# IntelliRoastSch.net
KiCad netlist of a schematic drawn in EAGLE
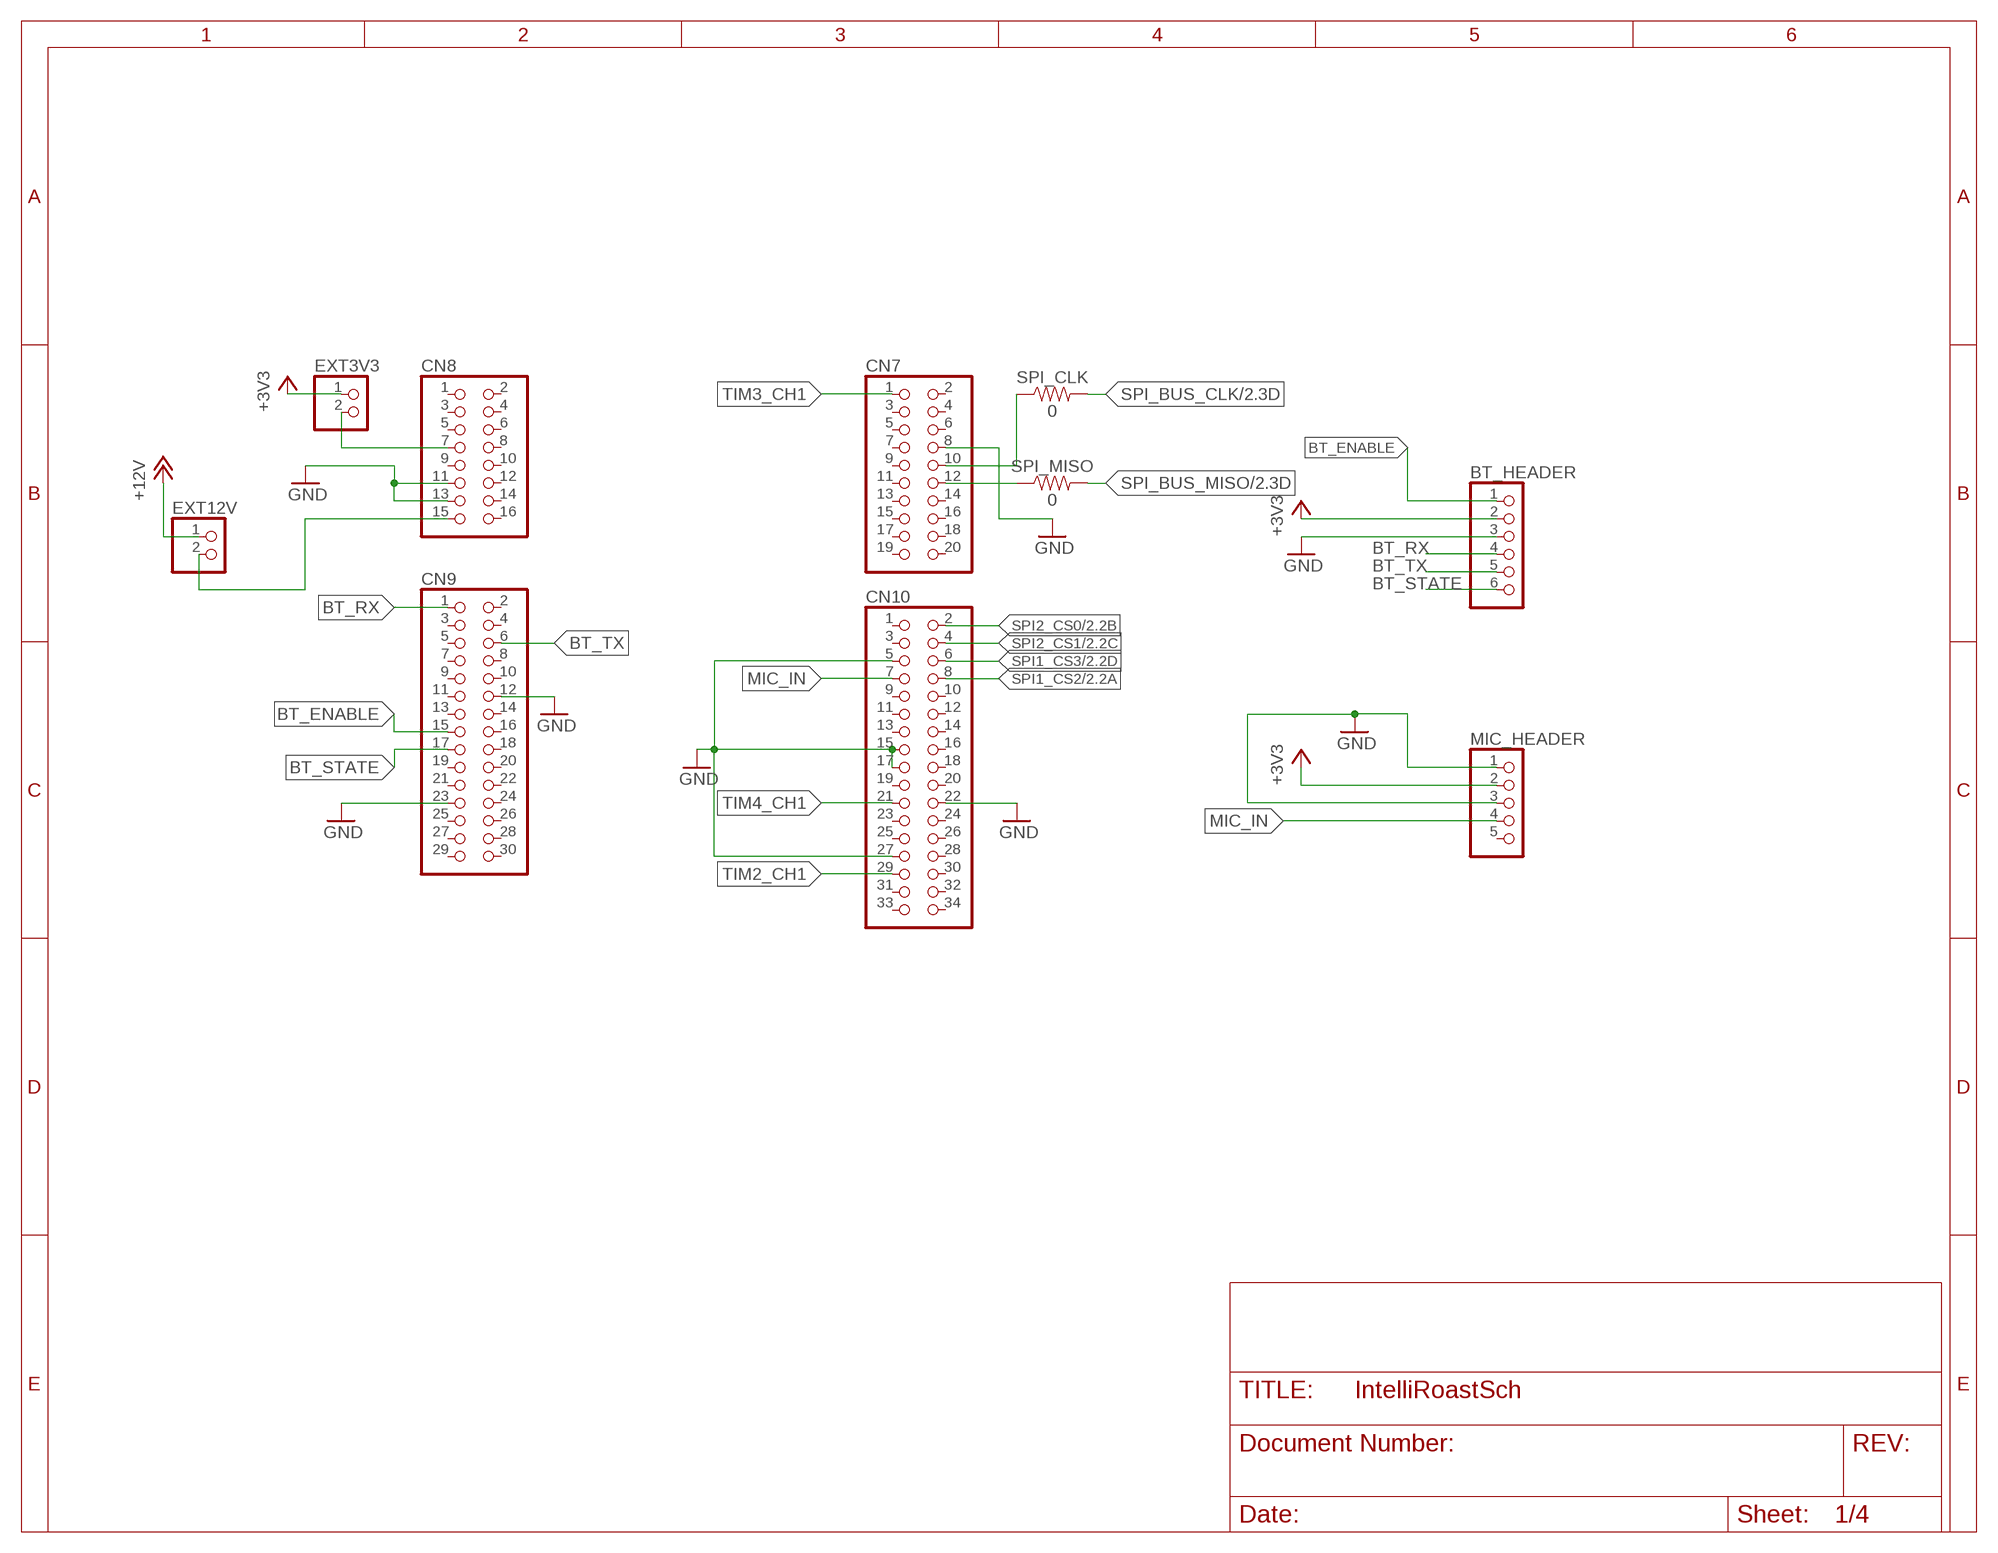
[diagram p0: schematic, sheet 1]
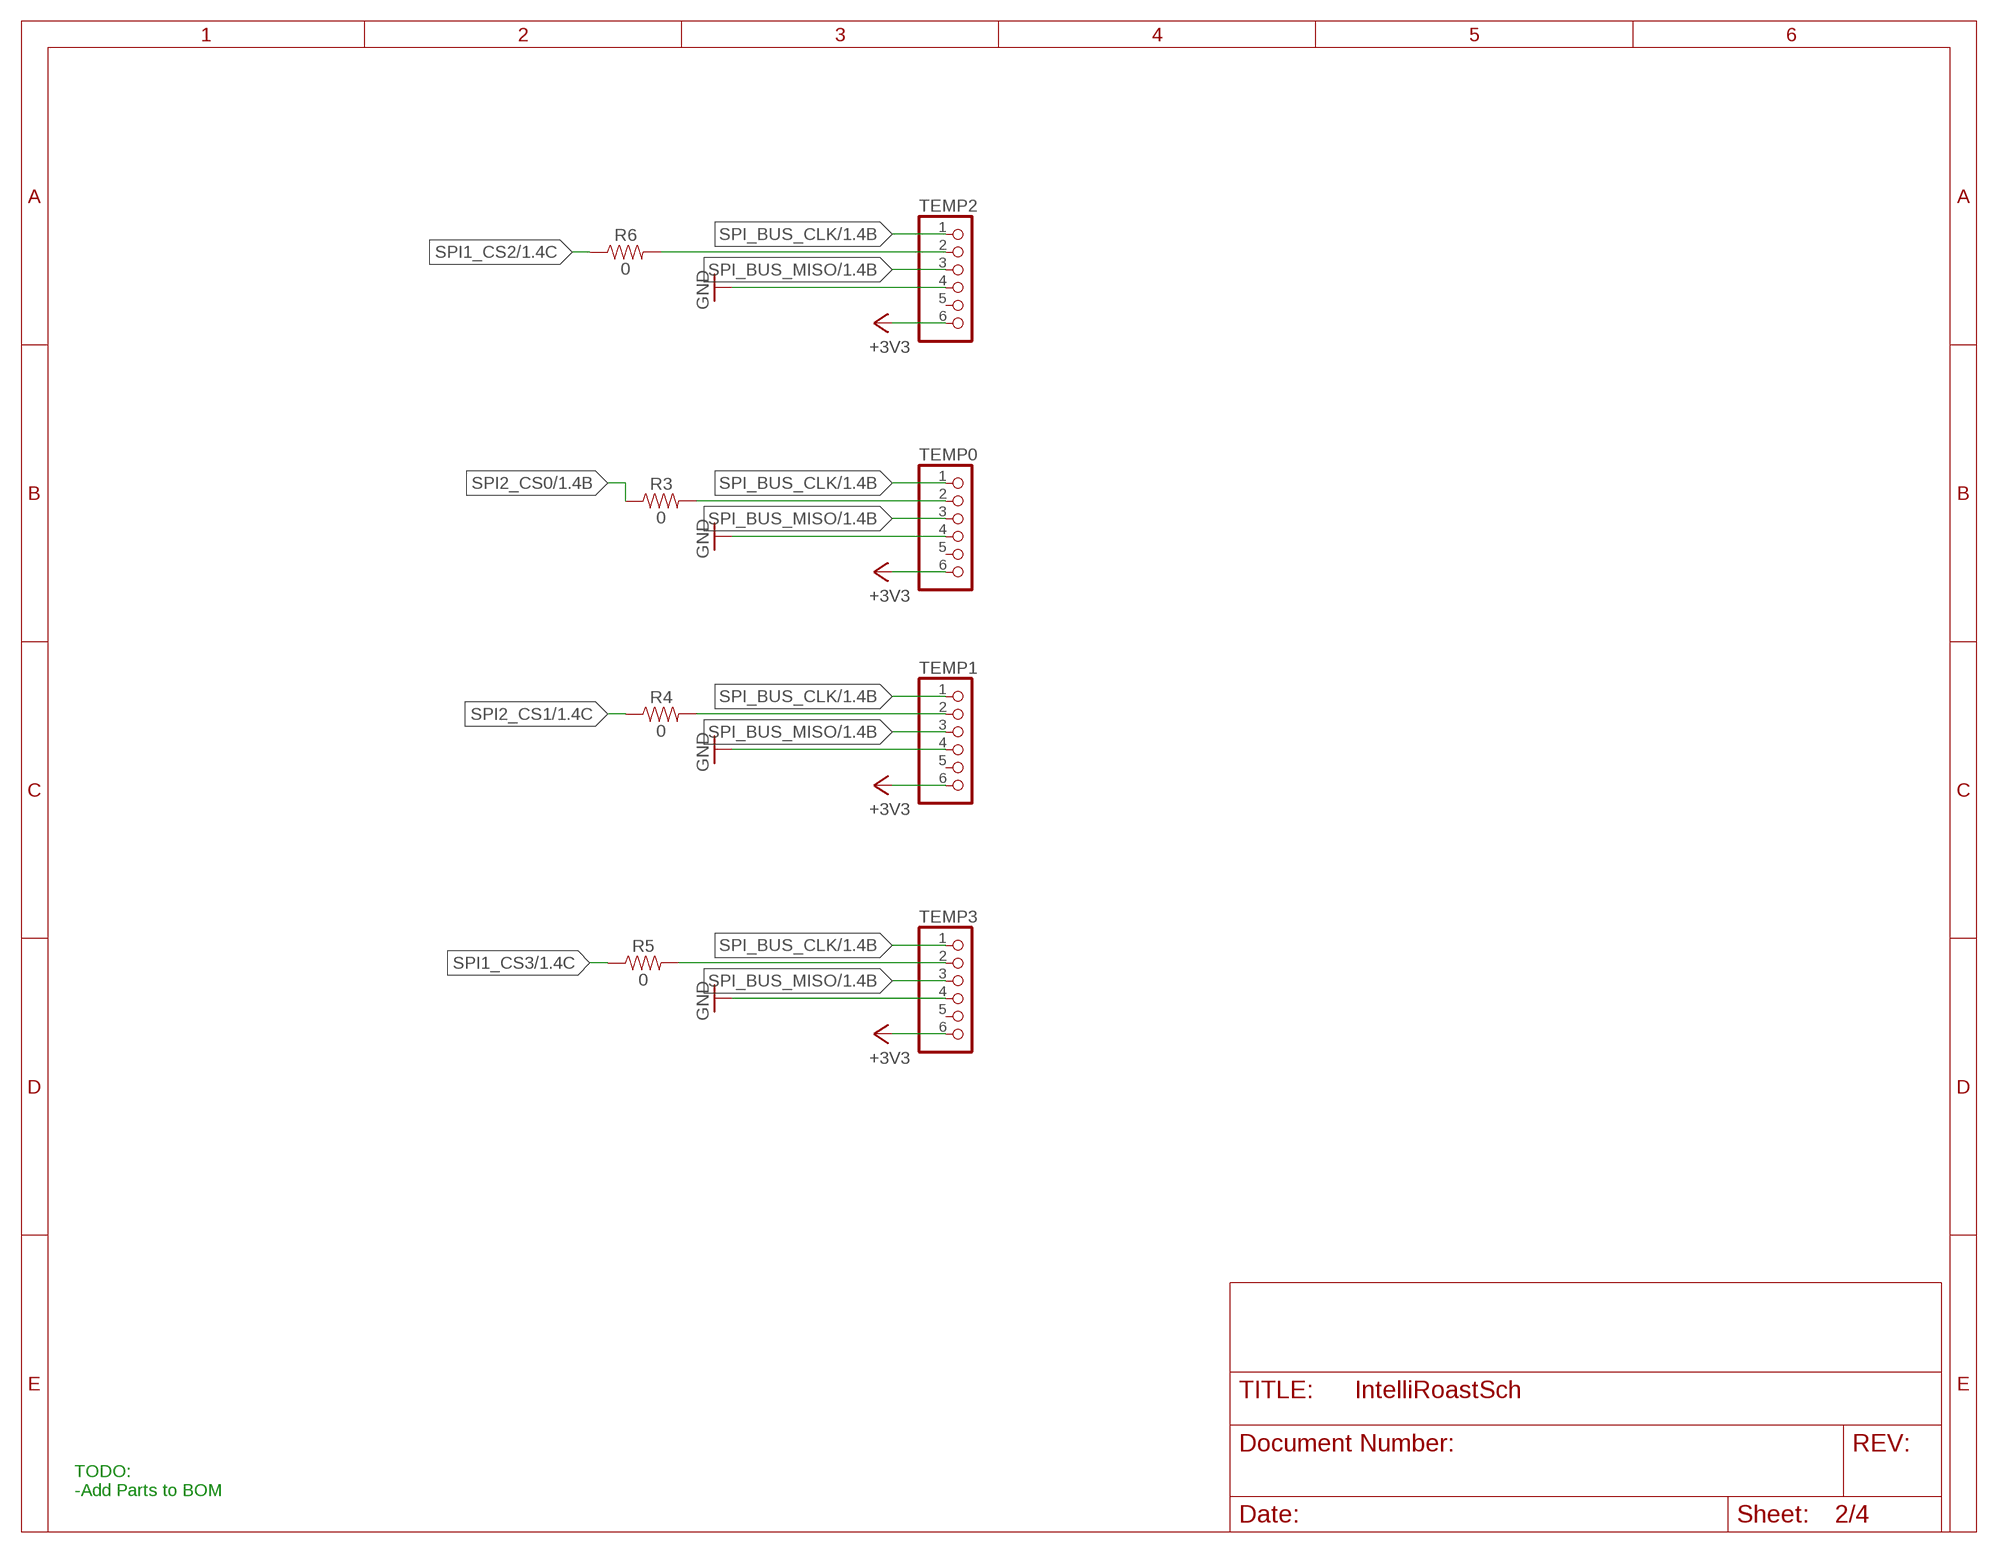
[diagram p1: schematic, sheet 2]
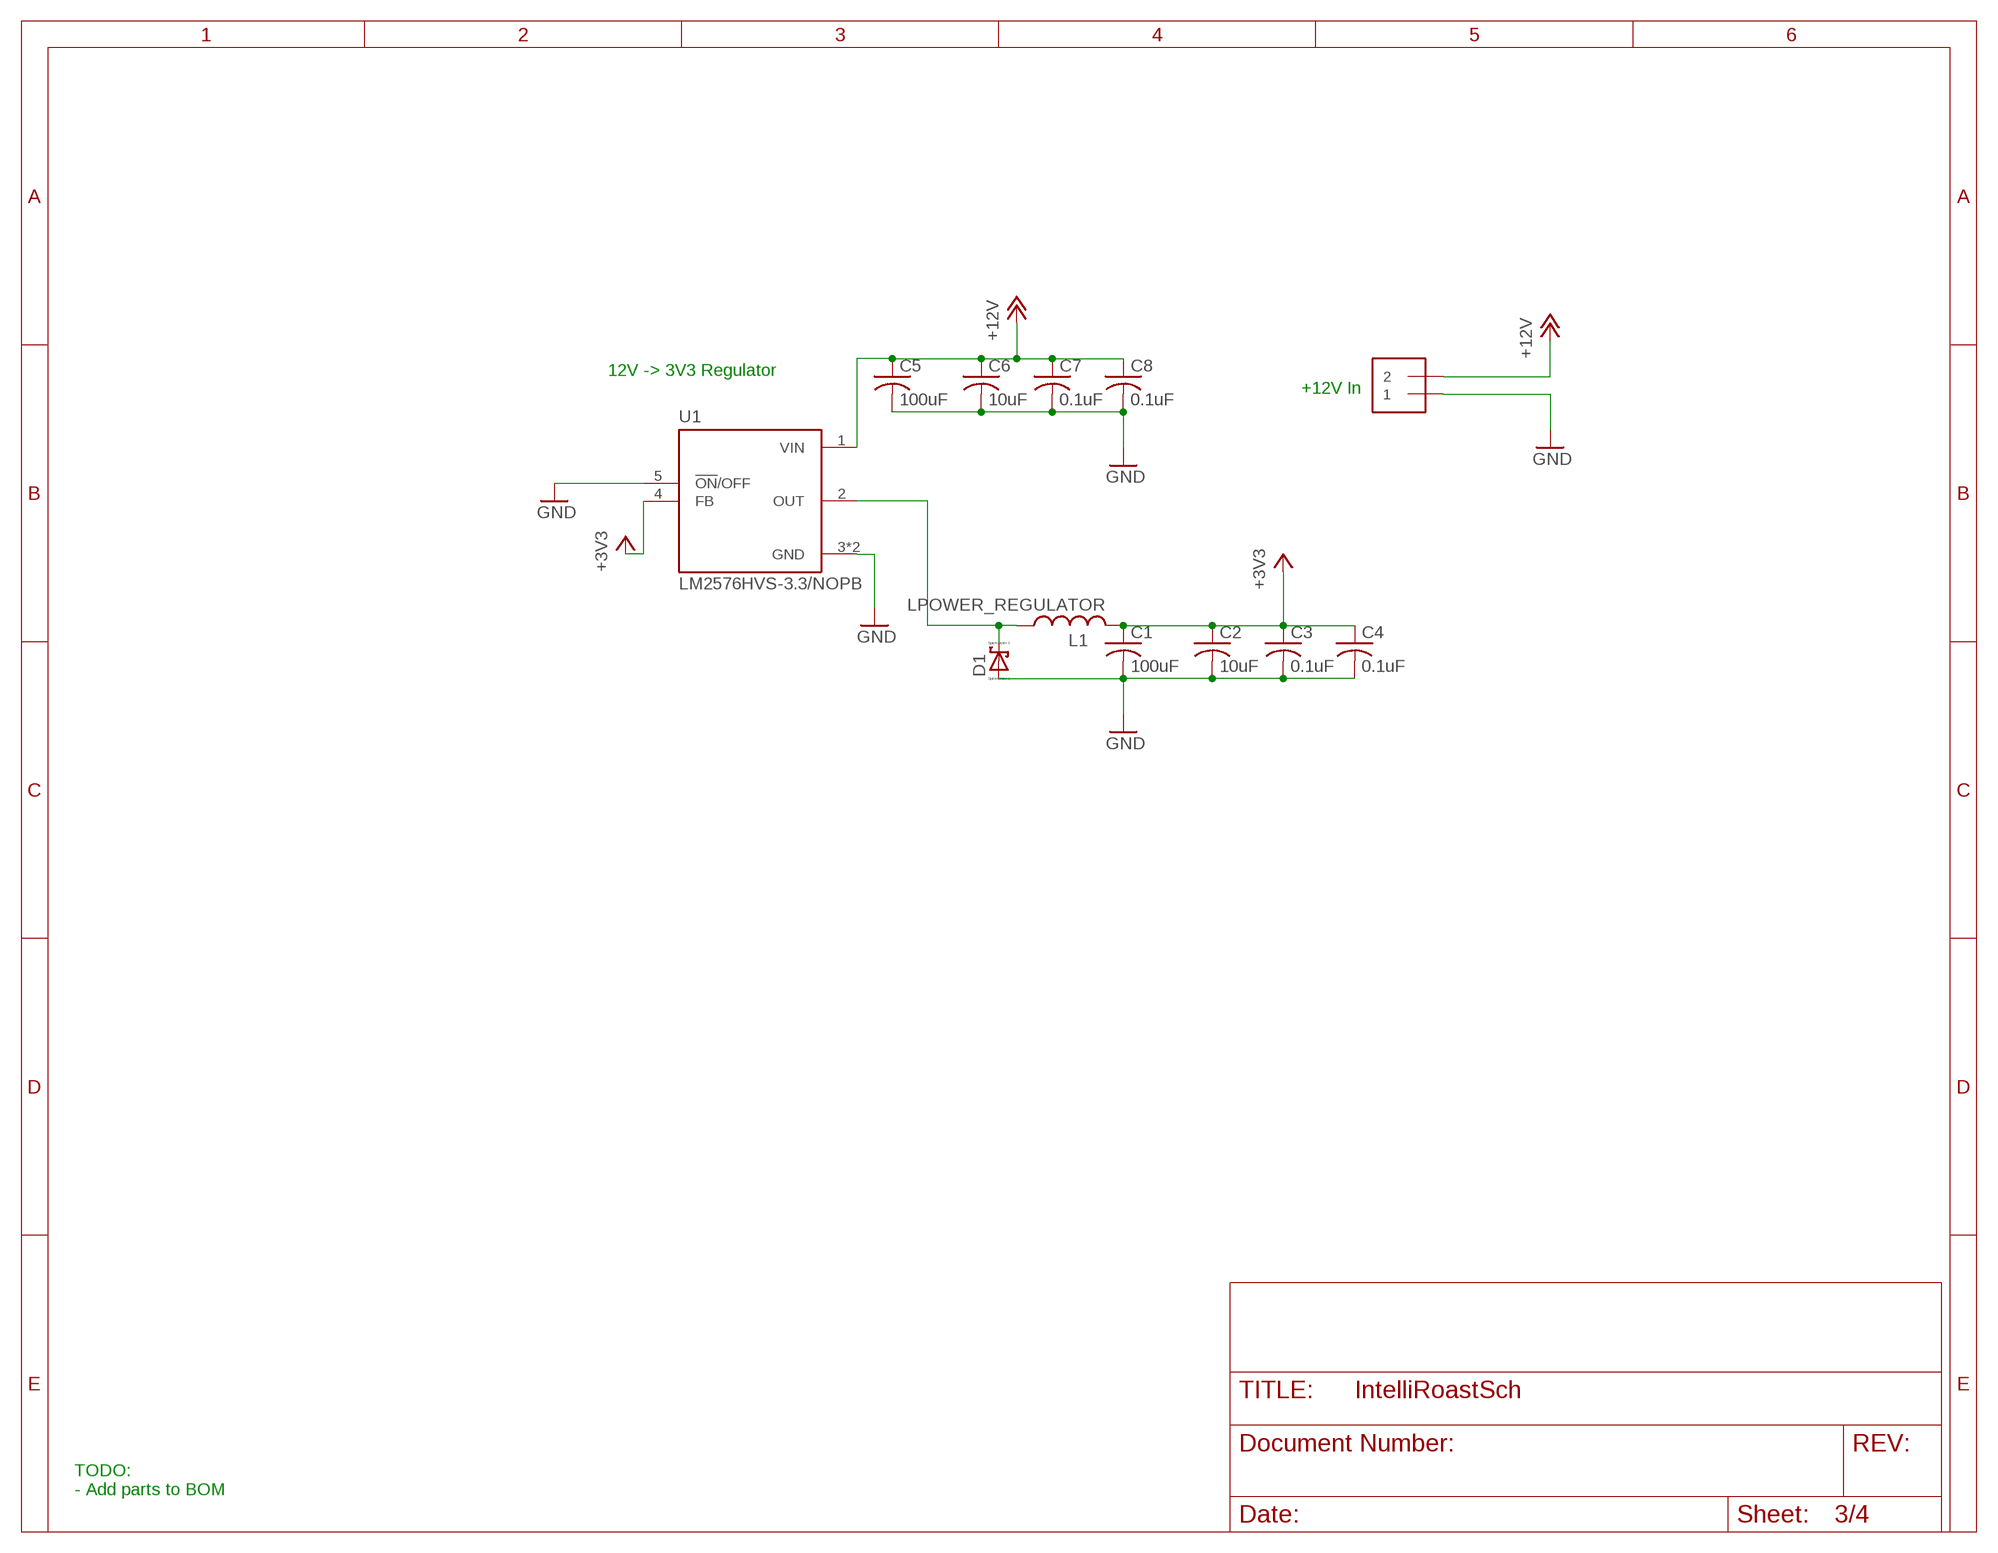
[diagram p2: schematic, sheet 3]
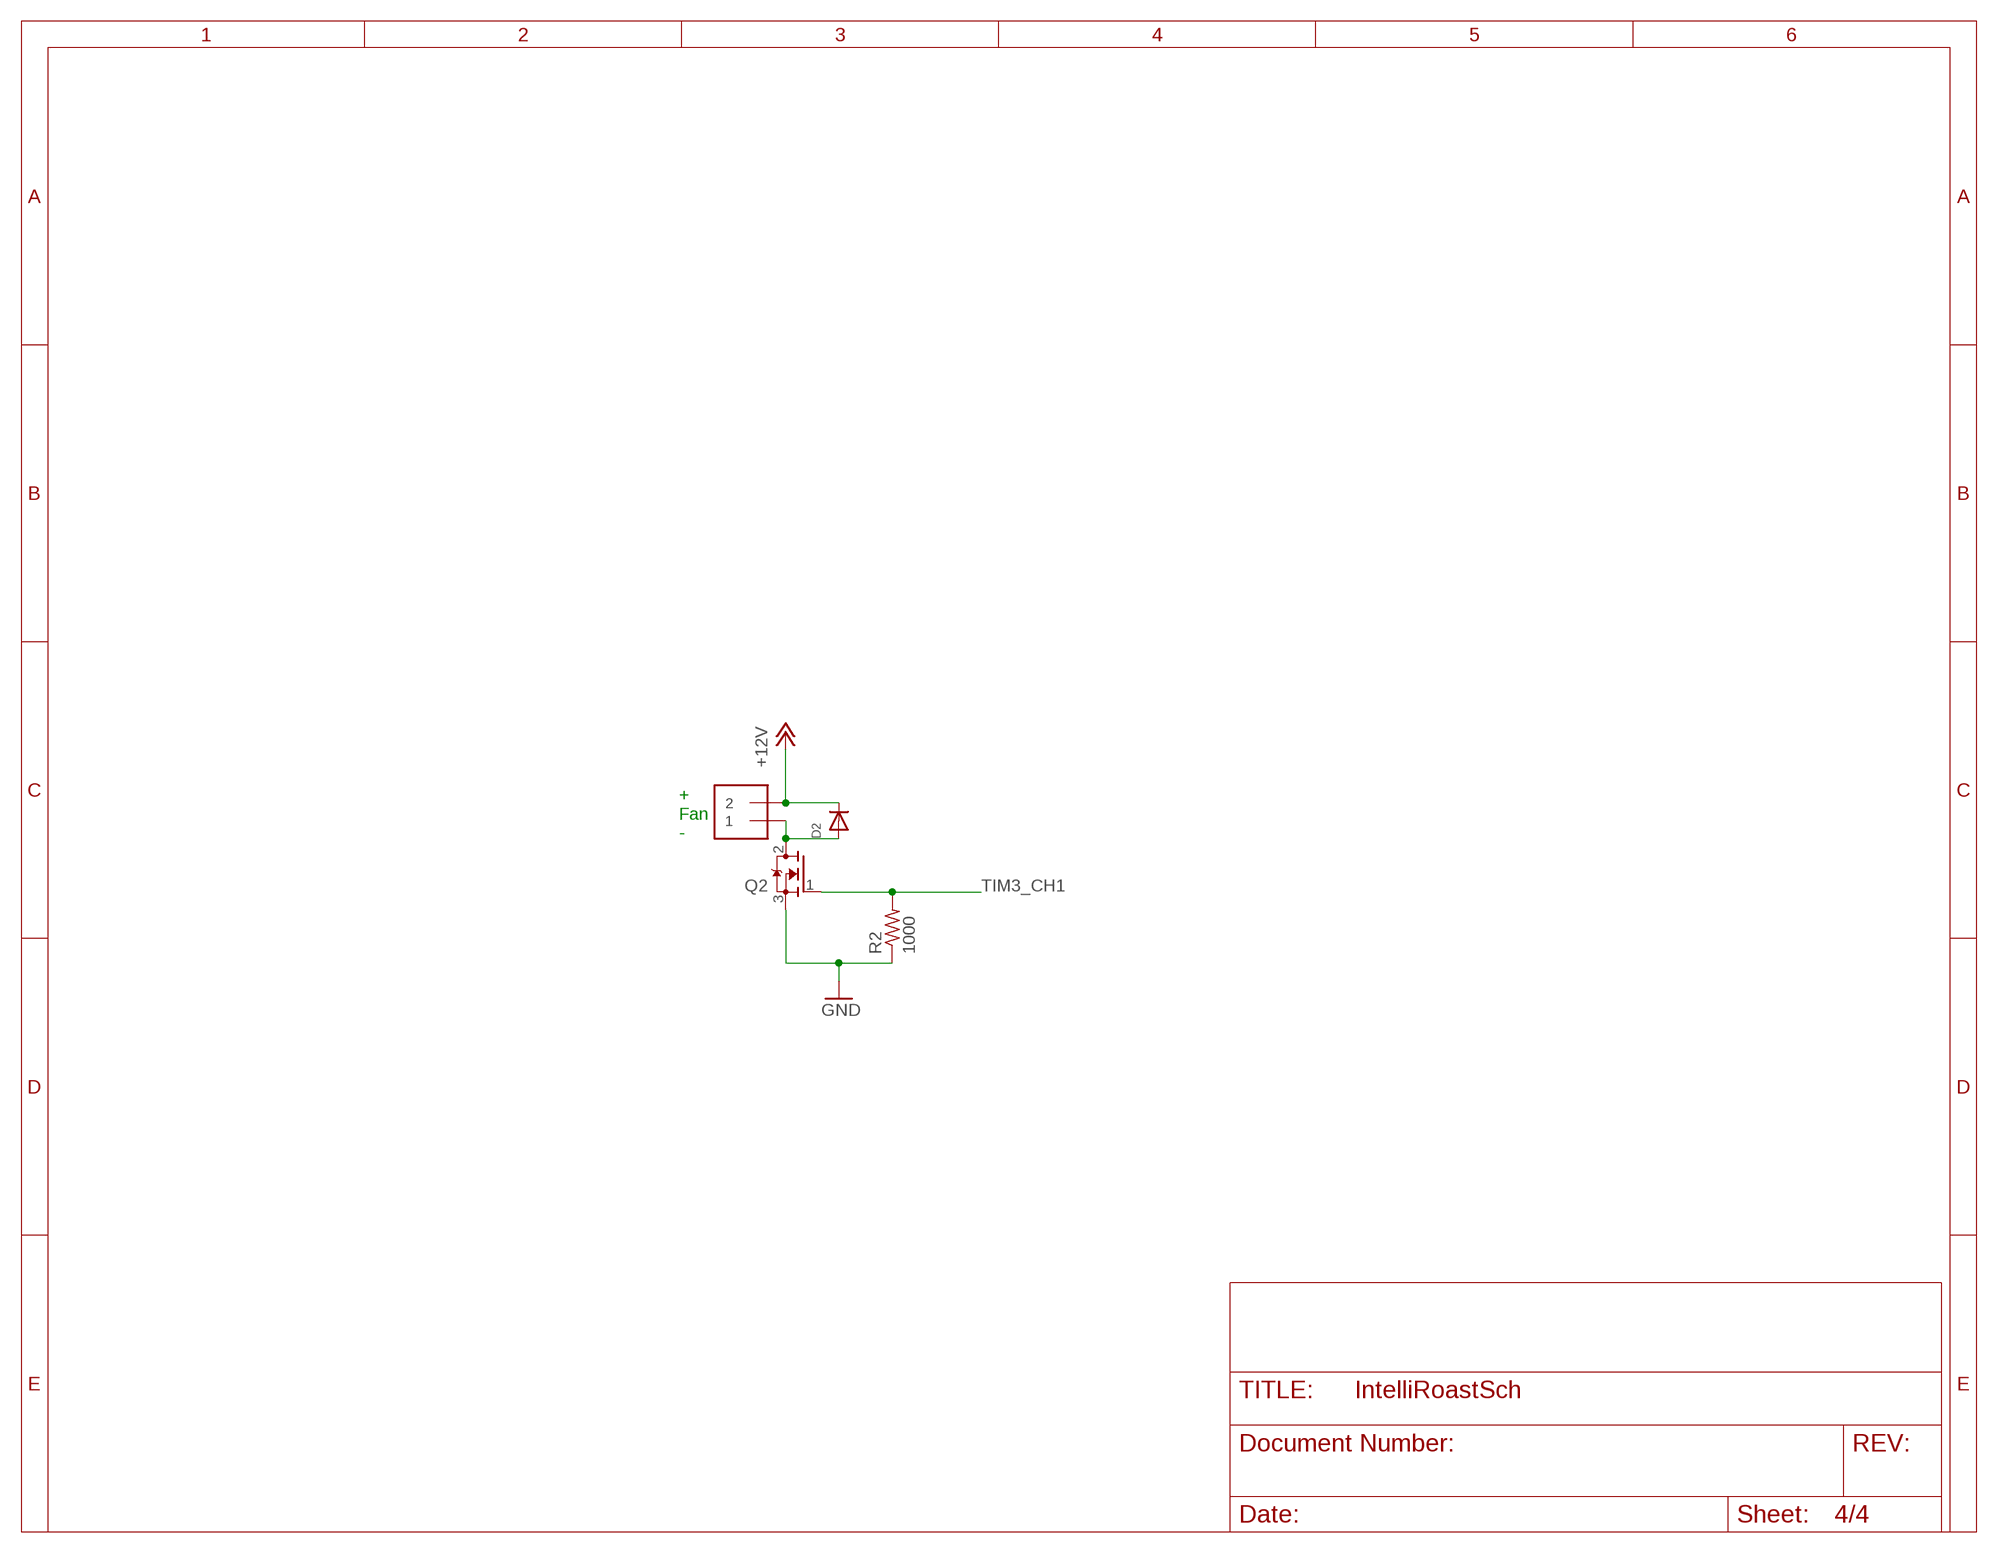
[diagram p3: schematic, sheet 4]

(export (version "E")
  (design (tool "Eeschema 10.0.6"))
  (components
    (comp (ref "C1")
      (value "100uF")
      (footprint "eagle-import:C1210")
      (libsource (lib "eagle-import") (part "C-USC1210"))
    )
    (comp (ref "C2")
      (value "10uF")
      (footprint "eagle-import:C0805")
      (libsource (lib "eagle-import") (part "C-USC0805"))
    )
    (comp (ref "C3")
      (value "0.1uF")
      (footprint "eagle-import:C0603")
      (libsource (lib "eagle-import") (part "C-USC0603"))
    )
    (comp (ref "C4")
      (value "0.1uF")
      (footprint "eagle-import:C0603")
      (libsource (lib "eagle-import") (part "C-USC0603"))
    )
    (comp (ref "C5")
      (value "100uF")
      (footprint "eagle-import:C1210")
      (libsource (lib "eagle-import") (part "C-USC1210"))
    )
    (comp (ref "C6")
      (value "10uF")
      (footprint "eagle-import:C0805")
      (libsource (lib "eagle-import") (part "C-USC0805"))
    )
    (comp (ref "C7")
      (value "0.1uF")
      (footprint "eagle-import:C0603")
      (libsource (lib "eagle-import") (part "C-USC0603"))
    )
    (comp (ref "C8")
      (value "0.1uF")
      (footprint "eagle-import:C0603")
      (libsource (lib "eagle-import") (part "C-USC0603"))
    )
    (comp (ref "D1")
      (value "SCHOTTKY-DIODESMC")
      (footprint "eagle-import:DIODE_SMC")
      (libsource (lib "eagle-import") (part "SCHOTTKY-DIODESMC"))
    )
    (comp (ref "L1")
      (value "LPOWER_REGULATOR")
      (footprint "eagle-import:L74477020")
      (libsource (lib "eagle-import") (part "LPOWER_REGULATOR"))
    )
    (comp (ref "PWR_IN")
      (value "1X2-3.5MM")
      (footprint "eagle-import:1X2-3.5MM")
      (libsource (lib "eagle-import") (part "1X2-3.5MM"))
    )
    (comp (ref "U1")
      (value "LM2576HVS-3.3/NOPB")
      (footprint "eagle-import:TO170P1435X465-6N")
      (fields (field (name "MF") "Texas Instruments"))
      (libsource (lib "eagle-import") (part "LM2576HVS-3.3/NOPB"))
    )
    (comp (ref "R3")
      (value "0")
      (footprint "eagle-import:0603")
      (libsource (lib "eagle-import") (part "0OHM-0603-1/10W-5%"))
    )
    (comp (ref "R4")
      (value "0")
      (footprint "eagle-import:0603")
      (libsource (lib "eagle-import") (part "0OHM-0603-1/10W-5%"))
    )
    (comp (ref "R5")
      (value "0")
      (footprint "eagle-import:0603")
      (libsource (lib "eagle-import") (part "0OHM-0603-1/10W-5%"))
    )
    (comp (ref "R6")
      (value "0")
      (footprint "eagle-import:0603")
      (libsource (lib "eagle-import") (part "0OHM-0603-1/10W-5%"))
    )
    (comp (ref "TEMP0")
      (value "ADAFRUIT-MAX31855-BREAKOUT")
      (footprint "eagle-import:MAX31855_HEADER")
      (libsource (lib "eagle-import") (part "ADAFRUIT-MAX31855-BREAKOUT"))
    )
    (comp (ref "TEMP1")
      (value "ADAFRUIT-MAX31855-BREAKOUT")
      (footprint "eagle-import:MAX31855_HEADER")
      (libsource (lib "eagle-import") (part "ADAFRUIT-MAX31855-BREAKOUT"))
    )
    (comp (ref "TEMP2")
      (value "ADAFRUIT-MAX31855-BREAKOUT")
      (footprint "eagle-import:MAX31855_HEADER")
      (libsource (lib "eagle-import") (part "ADAFRUIT-MAX31855-BREAKOUT"))
    )
    (comp (ref "TEMP3")
      (value "ADAFRUIT-MAX31855-BREAKOUT")
      (footprint "eagle-import:MAX31855_HEADER")
      (libsource (lib "eagle-import") (part "ADAFRUIT-MAX31855-BREAKOUT"))
    )
    (comp (ref "D2")
      (value "DIODESMA")
      (footprint "eagle-import:SMADIODE")
      (libsource (lib "eagle-import") (part "DIODESMA"))
    )
    (comp (ref "FAN")
      (value "1X2-3.5MM")
      (footprint "eagle-import:1X2-3.5MM")
      (libsource (lib "eagle-import") (part "1X2-3.5MM"))
    )
    (comp (ref "Q2")
      (value "MOSFET-NGDS_TO220V")
      (footprint "eagle-import:TO220V")
      (libsource (lib "eagle-import") (part "MOSFET-NGDS_TO220V"))
    )
    (comp (ref "R2")
      (value "1000")
      (footprint "eagle-import:R0603")
      (libsource (lib "eagle-import") (part "R-US_R0603"))
    )
    (comp (ref "BT_HEADER")
      (value "HC-05-BREAKOUT")
      (footprint "eagle-import:HC-O5_HEADER")
      (libsource (lib "eagle-import") (part "HC-05-BREAKOUT"))
    )
    (comp (ref "CN7")
      (value "PINHD-2X10")
      (footprint "eagle-import:2X10")
      (libsource (lib "eagle-import") (part "PINHD-2X10"))
    )
    (comp (ref "CN8")
      (value "PINHD-2X8")
      (footprint "eagle-import:2X08")
      (libsource (lib "eagle-import") (part "PINHD-2X8"))
    )
    (comp (ref "CN9")
      (value "PINHD-2X15")
      (footprint "eagle-import:2X15")
      (libsource (lib "eagle-import") (part "PINHD-2X15"))
    )
    (comp (ref "CN10")
      (value "PINHD-2X17")
      (footprint "eagle-import:2X17")
      (libsource (lib "eagle-import") (part "PINHD-2X17"))
    )
    (comp (ref "EXT3V3")
      (value "PINHD-1X2")
      (footprint "eagle-import:1X02")
      (libsource (lib "eagle-import") (part "PINHD-1X2"))
    )
    (comp (ref "EXT12V")
      (value "PINHD-1X2")
      (footprint "eagle-import:1X02")
      (libsource (lib "eagle-import") (part "PINHD-1X2"))
    )
    (comp (ref "MIC_HEADER")
      (value "PINHD-1X5")
      (footprint "eagle-import:1X05")
      (libsource (lib "eagle-import") (part "PINHD-1X5"))
    )
    (comp (ref "SPI_CLK")
      (value "0")
      (footprint "eagle-import:0603")
      (libsource (lib "eagle-import") (part "0OHM-0603-1/10W-5%"))
    )
    (comp (ref "SPI_MISO")
      (value "0")
      (footprint "eagle-import:0603")
      (libsource (lib "eagle-import") (part "0OHM-0603-1/10W-5%"))
    )
  )
  (nets
    (net (code "1") (name "+3V3") (class "Default")
      (node (ref "BT_HEADER") (pin "2") (pinfunction "2_2") (pintype "passive"))
      (node (ref "C1") (pin "1") (pinfunction "1_1") (pintype "passive"))
      (node (ref "C2") (pin "1") (pinfunction "1_1") (pintype "passive"))
      (node (ref "C3") (pin "1") (pinfunction "1_1") (pintype "passive"))
      (node (ref "C4") (pin "1") (pinfunction "1_1") (pintype "passive"))
      (node (ref "EXT3V3") (pin "1") (pinfunction "1_1") (pintype "passive"))
      (node (ref "L1") (pin "2") (pinfunction "2_2") (pintype "passive"))
      (node (ref "MIC_HEADER") (pin "2") (pinfunction "2_2") (pintype "passive"))
      (node (ref "TEMP0") (pin "6") (pinfunction "6_6") (pintype "passive"))
      (node (ref "TEMP1") (pin "6") (pinfunction "6_6") (pintype "passive"))
      (node (ref "TEMP2") (pin "6") (pinfunction "6_6") (pintype "passive"))
      (node (ref "TEMP3") (pin "6") (pinfunction "6_6") (pintype "passive"))
      (node (ref "U1") (pin "4") (pinfunction "FB_4") (pintype "input"))
    )
    (net (code "2") (name "+12V") (class "Default")
      (node (ref "C5") (pin "1") (pinfunction "1_1") (pintype "passive"))
      (node (ref "C6") (pin "1") (pinfunction "1_1") (pintype "passive"))
      (node (ref "C7") (pin "1") (pinfunction "1_1") (pintype "passive"))
      (node (ref "C8") (pin "1") (pinfunction "1_1") (pintype "passive"))
      (node (ref "D2") (pin "C") (pinfunction "C_C") (pintype "passive"))
      (node (ref "EXT12V") (pin "1") (pinfunction "1_1") (pintype "passive"))
      (node (ref "FAN") (pin "2") (pinfunction "2_2") (pintype "passive"))
      (node (ref "PWR_IN") (pin "2") (pinfunction "2_2") (pintype "passive"))
      (node (ref "U1") (pin "1") (pinfunction "VIN_1") (pintype "power_in"))
    )
    (net (code "3") (name "BT_ENABLE") (class "Default")
      (node (ref "BT_HEADER") (pin "1") (pinfunction "1_1") (pintype "passive"))
      (node (ref "CN9") (pin "15") (pinfunction "15_15") (pintype "passive"))
    )
    (net (code "4") (name "BT_RX") (class "Default")
      (node (ref "BT_HEADER") (pin "4") (pinfunction "4_4") (pintype "passive"))
      (node (ref "CN9") (pin "1") (pinfunction "1_1") (pintype "passive"))
    )
    (net (code "5") (name "BT_STATE") (class "Default")
      (node (ref "BT_HEADER") (pin "6") (pinfunction "6_6") (pintype "passive"))
      (node (ref "CN9") (pin "17") (pinfunction "17_17") (pintype "passive"))
    )
    (net (code "6") (name "BT_TX") (class "Default")
      (node (ref "BT_HEADER") (pin "5") (pinfunction "5_5") (pintype "passive"))
      (node (ref "CN9") (pin "6") (pinfunction "6_6") (pintype "passive"))
    )
    (net (code "7") (name "GND") (class "Default")
      (node (ref "BT_HEADER") (pin "3") (pinfunction "3_3") (pintype "passive"))
      (node (ref "C1") (pin "2") (pinfunction "2_2") (pintype "passive"))
      (node (ref "C2") (pin "2") (pinfunction "2_2") (pintype "passive"))
      (node (ref "C3") (pin "2") (pinfunction "2_2") (pintype "passive"))
      (node (ref "C4") (pin "2") (pinfunction "2_2") (pintype "passive"))
      (node (ref "C5") (pin "2") (pinfunction "2_2") (pintype "passive"))
      (node (ref "C6") (pin "2") (pinfunction "2_2") (pintype "passive"))
      (node (ref "C7") (pin "2") (pinfunction "2_2") (pintype "passive"))
      (node (ref "C8") (pin "2") (pinfunction "2_2") (pintype "passive"))
      (node (ref "CN10") (pin "15") (pinfunction "15_15") (pintype "passive"))
      (node (ref "CN10") (pin "17") (pinfunction "17_17") (pintype "passive"))
      (node (ref "CN10") (pin "22") (pinfunction "22_22") (pintype "passive"))
      (node (ref "CN10") (pin "27") (pinfunction "27_27") (pintype "passive"))
      (node (ref "CN10") (pin "5") (pinfunction "5_5") (pintype "passive"))
      (node (ref "CN7") (pin "8") (pinfunction "8_8") (pintype "passive"))
      (node (ref "CN8") (pin "11") (pinfunction "11_11") (pintype "passive"))
      (node (ref "CN8") (pin "13") (pinfunction "13_13") (pintype "passive"))
      (node (ref "CN9") (pin "12") (pinfunction "12_12") (pintype "passive"))
      (node (ref "CN9") (pin "23") (pinfunction "23_23") (pintype "passive"))
      (node (ref "D1") (pin "A") (pinfunction "C_A") (pintype "passive"))
      (node (ref "MIC_HEADER") (pin "1") (pinfunction "1_1") (pintype "passive"))
      (node (ref "MIC_HEADER") (pin "3") (pinfunction "3_3") (pintype "passive"))
      (node (ref "PWR_IN") (pin "1") (pinfunction "1_1") (pintype "passive"))
      (node (ref "Q2") (pin "3") (pinfunction "S_3") (pintype "bidirectional"))
      (node (ref "R2") (pin "1") (pinfunction "1_1") (pintype "passive"))
      (node (ref "TEMP0") (pin "4") (pinfunction "4_4") (pintype "passive"))
      (node (ref "TEMP1") (pin "4") (pinfunction "4_4") (pintype "passive"))
      (node (ref "TEMP2") (pin "4") (pinfunction "4_4") (pintype "passive"))
      (node (ref "TEMP3") (pin "4") (pinfunction "4_4") (pintype "passive"))
      (node (ref "U1") (pin "3") (pinfunction "GND_3") (pintype "power_in"))
      (node (ref "U1") (pin "5") (pinfunction "~{ON}/OFF_5") (pintype "input"))
      (node (ref "U1") (pin "6") (pinfunction "GND_6") (pintype "power_in"))
    )
    (net (code "8") (name "MIC_IN") (class "Default")
      (node (ref "CN10") (pin "7") (pinfunction "7_7") (pintype "passive"))
      (node (ref "MIC_HEADER") (pin "4") (pinfunction "4_4") (pintype "passive"))
    )
    (net (code "9") (name "Net-(CN7-Pad10)") (class "Default")
      (node (ref "CN7") (pin "10") (pinfunction "10_10") (pintype "passive"))
      (node (ref "SPI_CLK") (pin "1") (pinfunction "1_1") (pintype "passive"))
    )
    (net (code "10") (name "Net-(CN7-Pad12)") (class "Default")
      (node (ref "CN7") (pin "12") (pinfunction "12_12") (pintype "passive"))
      (node (ref "SPI_MISO") (pin "1") (pinfunction "1_1") (pintype "passive"))
    )
    (net (code "11") (name "Net-(CN8-Pad7)") (class "Default")
      (node (ref "CN8") (pin "7") (pinfunction "7_7") (pintype "passive"))
      (node (ref "EXT3V3") (pin "2") (pinfunction "2_2") (pintype "passive"))
    )
    (net (code "12") (name "Net-(CN8-Pad15)") (class "Default")
      (node (ref "CN8") (pin "15") (pinfunction "15_15") (pintype "passive"))
      (node (ref "EXT12V") (pin "2") (pinfunction "2_2") (pintype "passive"))
    )
    (net (code "13") (name "Net-(D1-A)") (class "Default")
      (node (ref "D1") (pin "C") (pinfunction "A_C") (pintype "passive"))
      (node (ref "L1") (pin "1") (pinfunction "1_1") (pintype "passive"))
      (node (ref "U1") (pin "2") (pinfunction "OUT_2") (pintype "output"))
    )
    (net (code "14") (name "Net-(Q2-D)") (class "Default")
      (node (ref "D2") (pin "A") (pinfunction "A_A") (pintype "passive"))
      (node (ref "FAN") (pin "1") (pinfunction "1_1") (pintype "passive"))
      (node (ref "Q2") (pin "2") (pinfunction "D_2") (pintype "bidirectional"))
    )
    (net (code "15") (name "Net-(R3-Pad2)") (class "Default")
      (node (ref "R3") (pin "2") (pinfunction "2_2") (pintype "passive"))
      (node (ref "TEMP0") (pin "2") (pinfunction "2_2") (pintype "passive"))
    )
    (net (code "16") (name "Net-(R4-Pad2)") (class "Default")
      (node (ref "R4") (pin "2") (pinfunction "2_2") (pintype "passive"))
      (node (ref "TEMP1") (pin "2") (pinfunction "2_2") (pintype "passive"))
    )
    (net (code "17") (name "Net-(R5-Pad2)") (class "Default")
      (node (ref "R5") (pin "2") (pinfunction "2_2") (pintype "passive"))
      (node (ref "TEMP3") (pin "2") (pinfunction "2_2") (pintype "passive"))
    )
    (net (code "18") (name "Net-(R6-Pad2)") (class "Default")
      (node (ref "R6") (pin "2") (pinfunction "2_2") (pintype "passive"))
      (node (ref "TEMP2") (pin "2") (pinfunction "2_2") (pintype "passive"))
    )
    (net (code "19") (name "SPI1_CS2") (class "Default")
      (node (ref "CN10") (pin "8") (pinfunction "8_8") (pintype "passive"))
      (node (ref "R6") (pin "1") (pinfunction "1_1") (pintype "passive"))
    )
    (net (code "20") (name "SPI1_CS3") (class "Default")
      (node (ref "CN10") (pin "6") (pinfunction "6_6") (pintype "passive"))
      (node (ref "R5") (pin "1") (pinfunction "1_1") (pintype "passive"))
    )
    (net (code "21") (name "SPI2_CS0") (class "Default")
      (node (ref "CN10") (pin "2") (pinfunction "2_2") (pintype "passive"))
      (node (ref "R3") (pin "1") (pinfunction "1_1") (pintype "passive"))
    )
    (net (code "22") (name "SPI2_CS1") (class "Default")
      (node (ref "CN10") (pin "4") (pinfunction "4_4") (pintype "passive"))
      (node (ref "R4") (pin "1") (pinfunction "1_1") (pintype "passive"))
    )
    (net (code "23") (name "SPI_BUS_CLK") (class "Default")
      (node (ref "SPI_CLK") (pin "2") (pinfunction "2_2") (pintype "passive"))
      (node (ref "TEMP0") (pin "1") (pinfunction "1_1") (pintype "passive"))
      (node (ref "TEMP1") (pin "1") (pinfunction "1_1") (pintype "passive"))
      (node (ref "TEMP2") (pin "1") (pinfunction "1_1") (pintype "passive"))
      (node (ref "TEMP3") (pin "1") (pinfunction "1_1") (pintype "passive"))
    )
    (net (code "24") (name "SPI_BUS_MISO") (class "Default")
      (node (ref "SPI_MISO") (pin "2") (pinfunction "2_2") (pintype "passive"))
      (node (ref "TEMP0") (pin "3") (pinfunction "3_3") (pintype "passive"))
      (node (ref "TEMP1") (pin "3") (pinfunction "3_3") (pintype "passive"))
      (node (ref "TEMP2") (pin "3") (pinfunction "3_3") (pintype "passive"))
      (node (ref "TEMP3") (pin "3") (pinfunction "3_3") (pintype "passive"))
    )
    (net (code "25") (name "TIM2_CH1") (class "Default")
      (node (ref "CN10") (pin "29") (pinfunction "29_29") (pintype "passive"))
    )
    (net (code "26") (name "TIM3_CH1") (class "Default")
      (node (ref "CN7") (pin "1") (pinfunction "1_1") (pintype "passive"))
      (node (ref "Q2") (pin "1") (pinfunction "G_1") (pintype "bidirectional"))
      (node (ref "R2") (pin "2") (pinfunction "2_2") (pintype "passive"))
    )
    (net (code "27") (name "TIM4_CH1") (class "Default")
      (node (ref "CN10") (pin "21") (pinfunction "21_21") (pintype "passive"))
    )
    (net (code "28") (name "unconnected-(CN7-Pad2)") (class "Default")
      (node (ref "CN7") (pin "2") (pinfunction "2_2") (pintype "passive"))
    )
    (net (code "29") (name "unconnected-(CN7-Pad3)") (class "Default")
      (node (ref "CN7") (pin "3") (pinfunction "3_3") (pintype "passive"))
    )
    (net (code "30") (name "unconnected-(CN7-Pad4)") (class "Default")
      (node (ref "CN7") (pin "4") (pinfunction "4_4") (pintype "passive"))
    )
    (net (code "31") (name "unconnected-(CN7-Pad5)") (class "Default")
      (node (ref "CN7") (pin "5") (pinfunction "5_5") (pintype "passive"))
    )
    (net (code "32") (name "unconnected-(CN7-Pad6)") (class "Default")
      (node (ref "CN7") (pin "6") (pinfunction "6_6") (pintype "passive"))
    )
    (net (code "33") (name "unconnected-(CN7-Pad7)") (class "Default")
      (node (ref "CN7") (pin "7") (pinfunction "7_7") (pintype "passive"))
    )
    (net (code "34") (name "unconnected-(CN7-Pad9)") (class "Default")
      (node (ref "CN7") (pin "9") (pinfunction "9_9") (pintype "passive"))
    )
    (net (code "35") (name "unconnected-(CN7-Pad11)") (class "Default")
      (node (ref "CN7") (pin "11") (pinfunction "11_11") (pintype "passive"))
    )
    (net (code "36") (name "unconnected-(CN7-Pad13)") (class "Default")
      (node (ref "CN7") (pin "13") (pinfunction "13_13") (pintype "passive"))
    )
    (net (code "37") (name "unconnected-(CN7-Pad14)") (class "Default")
      (node (ref "CN7") (pin "14") (pinfunction "14_14") (pintype "passive"))
    )
    (net (code "38") (name "unconnected-(CN7-Pad15)") (class "Default")
      (node (ref "CN7") (pin "15") (pinfunction "15_15") (pintype "passive"))
    )
    (net (code "39") (name "unconnected-(CN7-Pad16)") (class "Default")
      (node (ref "CN7") (pin "16") (pinfunction "16_16") (pintype "passive"))
    )
    (net (code "40") (name "unconnected-(CN7-Pad17)") (class "Default")
      (node (ref "CN7") (pin "17") (pinfunction "17_17") (pintype "passive"))
    )
    (net (code "41") (name "unconnected-(CN7-Pad18)") (class "Default")
      (node (ref "CN7") (pin "18") (pinfunction "18_18") (pintype "passive"))
    )
    (net (code "42") (name "unconnected-(CN7-Pad19)") (class "Default")
      (node (ref "CN7") (pin "19") (pinfunction "19_19") (pintype "passive"))
    )
    (net (code "43") (name "unconnected-(CN7-Pad20)") (class "Default")
      (node (ref "CN7") (pin "20") (pinfunction "20_20") (pintype "passive"))
    )
    (net (code "44") (name "unconnected-(CN8-Pad1)") (class "Default")
      (node (ref "CN8") (pin "1") (pinfunction "1_1") (pintype "passive"))
    )
    (net (code "45") (name "unconnected-(CN8-Pad2)") (class "Default")
      (node (ref "CN8") (pin "2") (pinfunction "2_2") (pintype "passive"))
    )
    (net (code "46") (name "unconnected-(CN8-Pad3)") (class "Default")
      (node (ref "CN8") (pin "3") (pinfunction "3_3") (pintype "passive"))
    )
    (net (code "47") (name "unconnected-(CN8-Pad4)") (class "Default")
      (node (ref "CN8") (pin "4") (pinfunction "4_4") (pintype "passive"))
    )
    (net (code "48") (name "unconnected-(CN8-Pad5)") (class "Default")
      (node (ref "CN8") (pin "5") (pinfunction "5_5") (pintype "passive"))
    )
    (net (code "49") (name "unconnected-(CN8-Pad6)") (class "Default")
      (node (ref "CN8") (pin "6") (pinfunction "6_6") (pintype "passive"))
    )
    (net (code "50") (name "unconnected-(CN8-Pad8)") (class "Default")
      (node (ref "CN8") (pin "8") (pinfunction "8_8") (pintype "passive"))
    )
    (net (code "51") (name "unconnected-(CN8-Pad9)") (class "Default")
      (node (ref "CN8") (pin "9") (pinfunction "9_9") (pintype "passive"))
    )
    (net (code "52") (name "unconnected-(CN8-Pad10)") (class "Default")
      (node (ref "CN8") (pin "10") (pinfunction "10_10") (pintype "passive"))
    )
    (net (code "53") (name "unconnected-(CN8-Pad12)") (class "Default")
      (node (ref "CN8") (pin "12") (pinfunction "12_12") (pintype "passive"))
    )
    (net (code "54") (name "unconnected-(CN8-Pad14)") (class "Default")
      (node (ref "CN8") (pin "14") (pinfunction "14_14") (pintype "passive"))
    )
    (net (code "55") (name "unconnected-(CN8-Pad16)") (class "Default")
      (node (ref "CN8") (pin "16") (pinfunction "16_16") (pintype "passive"))
    )
    (net (code "56") (name "unconnected-(CN9-Pad2)") (class "Default")
      (node (ref "CN9") (pin "2") (pinfunction "2_2") (pintype "passive"))
    )
    (net (code "57") (name "unconnected-(CN9-Pad3)") (class "Default")
      (node (ref "CN9") (pin "3") (pinfunction "3_3") (pintype "passive"))
    )
    (net (code "58") (name "unconnected-(CN9-Pad4)") (class "Default")
      (node (ref "CN9") (pin "4") (pinfunction "4_4") (pintype "passive"))
    )
    (net (code "59") (name "unconnected-(CN9-Pad5)") (class "Default")
      (node (ref "CN9") (pin "5") (pinfunction "5_5") (pintype "passive"))
    )
    (net (code "60") (name "unconnected-(CN9-Pad7)") (class "Default")
      (node (ref "CN9") (pin "7") (pinfunction "7_7") (pintype "passive"))
    )
    (net (code "61") (name "unconnected-(CN9-Pad8)") (class "Default")
      (node (ref "CN9") (pin "8") (pinfunction "8_8") (pintype "passive"))
    )
    (net (code "62") (name "unconnected-(CN9-Pad9)") (class "Default")
      (node (ref "CN9") (pin "9") (pinfunction "9_9") (pintype "passive"))
    )
    (net (code "63") (name "unconnected-(CN9-Pad10)") (class "Default")
      (node (ref "CN9") (pin "10") (pinfunction "10_10") (pintype "passive"))
    )
    (net (code "64") (name "unconnected-(CN9-Pad11)") (class "Default")
      (node (ref "CN9") (pin "11") (pinfunction "11_11") (pintype "passive"))
    )
    (net (code "65") (name "unconnected-(CN9-Pad13)") (class "Default")
      (node (ref "CN9") (pin "13") (pinfunction "13_13") (pintype "passive"))
    )
    (net (code "66") (name "unconnected-(CN9-Pad14)") (class "Default")
      (node (ref "CN9") (pin "14") (pinfunction "14_14") (pintype "passive"))
    )
    (net (code "67") (name "unconnected-(CN9-Pad16)") (class "Default")
      (node (ref "CN9") (pin "16") (pinfunction "16_16") (pintype "passive"))
    )
    (net (code "68") (name "unconnected-(CN9-Pad18)") (class "Default")
      (node (ref "CN9") (pin "18") (pinfunction "18_18") (pintype "passive"))
    )
    (net (code "69") (name "unconnected-(CN9-Pad19)") (class "Default")
      (node (ref "CN9") (pin "19") (pinfunction "19_19") (pintype "passive"))
    )
    (net (code "70") (name "unconnected-(CN9-Pad20)") (class "Default")
      (node (ref "CN9") (pin "20") (pinfunction "20_20") (pintype "passive"))
    )
    (net (code "71") (name "unconnected-(CN9-Pad21)") (class "Default")
      (node (ref "CN9") (pin "21") (pinfunction "21_21") (pintype "passive"))
    )
    (net (code "72") (name "unconnected-(CN9-Pad22)") (class "Default")
      (node (ref "CN9") (pin "22") (pinfunction "22_22") (pintype "passive"))
    )
    (net (code "73") (name "unconnected-(CN9-Pad24)") (class "Default")
      (node (ref "CN9") (pin "24") (pinfunction "24_24") (pintype "passive"))
    )
    (net (code "74") (name "unconnected-(CN9-Pad25)") (class "Default")
      (node (ref "CN9") (pin "25") (pinfunction "25_25") (pintype "passive"))
    )
    (net (code "75") (name "unconnected-(CN9-Pad26)") (class "Default")
      (node (ref "CN9") (pin "26") (pinfunction "26_26") (pintype "passive"))
    )
    (net (code "76") (name "unconnected-(CN9-Pad27)") (class "Default")
      (node (ref "CN9") (pin "27") (pinfunction "27_27") (pintype "passive"))
    )
    (net (code "77") (name "unconnected-(CN9-Pad28)") (class "Default")
      (node (ref "CN9") (pin "28") (pinfunction "28_28") (pintype "passive"))
    )
    (net (code "78") (name "unconnected-(CN9-Pad29)") (class "Default")
      (node (ref "CN9") (pin "29") (pinfunction "29_29") (pintype "passive"))
    )
    (net (code "79") (name "unconnected-(CN9-Pad30)") (class "Default")
      (node (ref "CN9") (pin "30") (pinfunction "30_30") (pintype "passive"))
    )
    (net (code "80") (name "unconnected-(CN10-Pad1)") (class "Default")
      (node (ref "CN10") (pin "1") (pinfunction "1_1") (pintype "passive"))
    )
    (net (code "81") (name "unconnected-(CN10-Pad3)") (class "Default")
      (node (ref "CN10") (pin "3") (pinfunction "3_3") (pintype "passive"))
    )
    (net (code "82") (name "unconnected-(CN10-Pad9)") (class "Default")
      (node (ref "CN10") (pin "9") (pinfunction "9_9") (pintype "passive"))
    )
    (net (code "83") (name "unconnected-(CN10-Pad10)") (class "Default")
      (node (ref "CN10") (pin "10") (pinfunction "10_10") (pintype "passive"))
    )
    (net (code "84") (name "unconnected-(CN10-Pad11)") (class "Default")
      (node (ref "CN10") (pin "11") (pinfunction "11_11") (pintype "passive"))
    )
    (net (code "85") (name "unconnected-(CN10-Pad12)") (class "Default")
      (node (ref "CN10") (pin "12") (pinfunction "12_12") (pintype "passive"))
    )
    (net (code "86") (name "unconnected-(CN10-Pad13)") (class "Default")
      (node (ref "CN10") (pin "13") (pinfunction "13_13") (pintype "passive"))
    )
    (net (code "87") (name "unconnected-(CN10-Pad14)") (class "Default")
      (node (ref "CN10") (pin "14") (pinfunction "14_14") (pintype "passive"))
    )
    (net (code "88") (name "unconnected-(CN10-Pad16)") (class "Default")
      (node (ref "CN10") (pin "16") (pinfunction "16_16") (pintype "passive"))
    )
    (net (code "89") (name "unconnected-(CN10-Pad18)") (class "Default")
      (node (ref "CN10") (pin "18") (pinfunction "18_18") (pintype "passive"))
    )
    (net (code "90") (name "unconnected-(CN10-Pad19)") (class "Default")
      (node (ref "CN10") (pin "19") (pinfunction "19_19") (pintype "passive"))
    )
    (net (code "91") (name "unconnected-(CN10-Pad20)") (class "Default")
      (node (ref "CN10") (pin "20") (pinfunction "20_20") (pintype "passive"))
    )
    (net (code "92") (name "unconnected-(CN10-Pad23)") (class "Default")
      (node (ref "CN10") (pin "23") (pinfunction "23_23") (pintype "passive"))
    )
    (net (code "93") (name "unconnected-(CN10-Pad24)") (class "Default")
      (node (ref "CN10") (pin "24") (pinfunction "24_24") (pintype "passive"))
    )
    (net (code "94") (name "unconnected-(CN10-Pad25)") (class "Default")
      (node (ref "CN10") (pin "25") (pinfunction "25_25") (pintype "passive"))
    )
    (net (code "95") (name "unconnected-(CN10-Pad26)") (class "Default")
      (node (ref "CN10") (pin "26") (pinfunction "26_26") (pintype "passive"))
    )
    (net (code "96") (name "unconnected-(CN10-Pad28)") (class "Default")
      (node (ref "CN10") (pin "28") (pinfunction "28_28") (pintype "passive"))
    )
    (net (code "97") (name "unconnected-(CN10-Pad30)") (class "Default")
      (node (ref "CN10") (pin "30") (pinfunction "30_30") (pintype "passive"))
    )
    (net (code "98") (name "unconnected-(CN10-Pad31)") (class "Default")
      (node (ref "CN10") (pin "31") (pinfunction "31_31") (pintype "passive"))
    )
    (net (code "99") (name "unconnected-(CN10-Pad32)") (class "Default")
      (node (ref "CN10") (pin "32") (pinfunction "32_32") (pintype "passive"))
    )
    (net (code "100") (name "unconnected-(CN10-Pad33)") (class "Default")
      (node (ref "CN10") (pin "33") (pinfunction "33_33") (pintype "passive"))
    )
    (net (code "101") (name "unconnected-(CN10-Pad34)") (class "Default")
      (node (ref "CN10") (pin "34") (pinfunction "34_34") (pintype "passive"))
    )
    (net (code "102") (name "unconnected-(MIC_HEADER-Pad5)") (class "Default")
      (node (ref "MIC_HEADER") (pin "5") (pinfunction "5_5") (pintype "passive"))
    )
    (net (code "103") (name "unconnected-(TEMP0-Pad5)") (class "Default")
      (node (ref "TEMP0") (pin "5") (pinfunction "5_5") (pintype "passive"))
    )
    (net (code "104") (name "unconnected-(TEMP1-Pad5)") (class "Default")
      (node (ref "TEMP1") (pin "5") (pinfunction "5_5") (pintype "passive"))
    )
    (net (code "105") (name "unconnected-(TEMP2-Pad5)") (class "Default")
      (node (ref "TEMP2") (pin "5") (pinfunction "5_5") (pintype "passive"))
    )
    (net (code "106") (name "unconnected-(TEMP3-Pad5)") (class "Default")
      (node (ref "TEMP3") (pin "5") (pinfunction "5_5") (pintype "passive"))
    )
  )
)
